# TUSB8041_Misc_2.net
KiCad netlist of a schematic drawn in Altium Designer
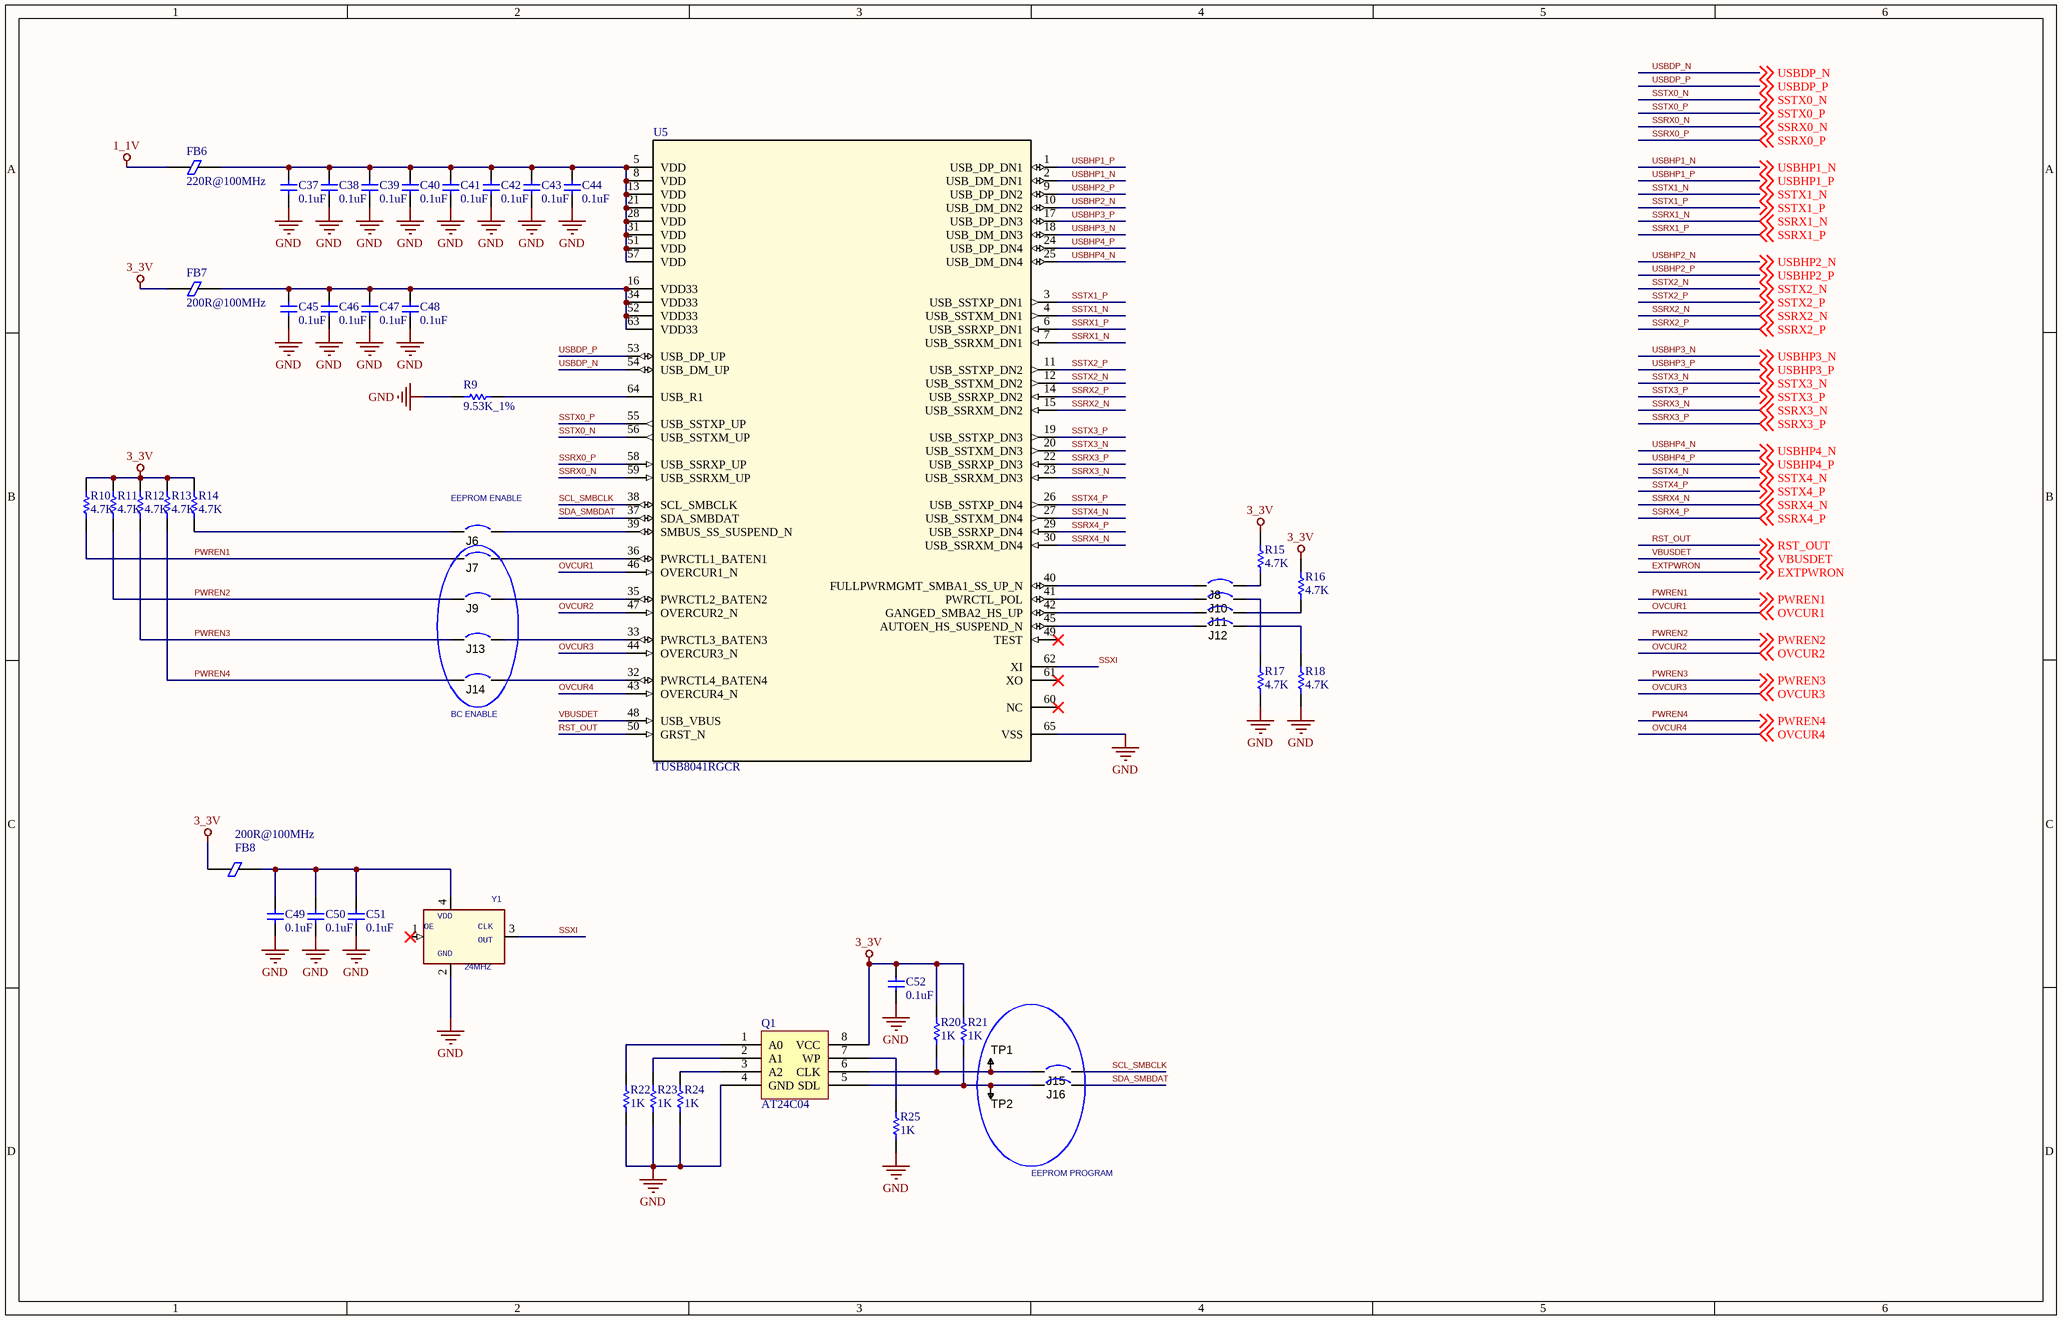
[diagram p0: TUSB8041_Misc_2.SchDoc]

(export (version "E")
  (design (tool "Eeschema 10.0.6"))
  (components
    (comp (ref "C37")
      (value "0.1uF")
      (footprint "CAP0402")
      (description "Capacitor")
      (fields (field (name "PUBLISHER") "Altium Limited"))
      (libsource (lib "TUSB8041_USB_3.0_Hub") (part "CAP"))
    )
    (comp (ref "C38")
      (value "0.1uF")
      (footprint "CAP0402")
      (description "Capacitor")
      (fields (field (name "PUBLISHER") "Altium Limited"))
      (libsource (lib "TUSB8041_USB_3.0_Hub") (part "CAP"))
    )
    (comp (ref "C39")
      (value "0.1uF")
      (footprint "CAP0402")
      (description "Capacitor")
      (fields (field (name "PUBLISHER") "Altium Limited"))
      (libsource (lib "TUSB8041_USB_3.0_Hub") (part "CAP"))
    )
    (comp (ref "C40")
      (value "0.1uF")
      (footprint "CAP0402")
      (description "Capacitor")
      (fields (field (name "PUBLISHER") "Altium Limited"))
      (libsource (lib "TUSB8041_USB_3.0_Hub") (part "CAP"))
    )
    (comp (ref "C41")
      (value "0.1uF")
      (footprint "CAP0402")
      (description "Capacitor")
      (fields (field (name "PUBLISHER") "Altium Limited"))
      (libsource (lib "TUSB8041_USB_3.0_Hub") (part "CAP"))
    )
    (comp (ref "C42")
      (value "0.1uF")
      (footprint "CAP0402")
      (description "Capacitor")
      (fields (field (name "PUBLISHER") "Altium Limited"))
      (libsource (lib "TUSB8041_USB_3.0_Hub") (part "CAP"))
    )
    (comp (ref "C43")
      (value "0.1uF")
      (footprint "CAP0402")
      (description "Capacitor")
      (fields (field (name "PUBLISHER") "Altium Limited"))
      (libsource (lib "TUSB8041_USB_3.0_Hub") (part "CAP"))
    )
    (comp (ref "C44")
      (value "0.1uF")
      (footprint "CAP0402")
      (description "Capacitor")
      (fields (field (name "PUBLISHER") "Altium Limited"))
      (libsource (lib "TUSB8041_USB_3.0_Hub") (part "CAP"))
    )
    (comp (ref "C45")
      (value "0.1uF")
      (footprint "CAP0402")
      (description "Capacitor")
      (fields (field (name "PUBLISHER") "Altium Limited"))
      (libsource (lib "TUSB8041_USB_3.0_Hub") (part "CAP"))
    )
    (comp (ref "C46")
      (value "0.1uF")
      (footprint "CAP0402")
      (description "Capacitor")
      (fields (field (name "PUBLISHER") "Altium Limited"))
      (libsource (lib "TUSB8041_USB_3.0_Hub") (part "CAP"))
    )
    (comp (ref "C47")
      (value "0.1uF")
      (footprint "CAP0402")
      (description "Capacitor")
      (fields (field (name "PUBLISHER") "Altium Limited"))
      (libsource (lib "TUSB8041_USB_3.0_Hub") (part "CAP"))
    )
    (comp (ref "C48")
      (value "0.1uF")
      (footprint "CAP0402")
      (description "Capacitor")
      (fields (field (name "PUBLISHER") "Altium Limited"))
      (libsource (lib "TUSB8041_USB_3.0_Hub") (part "CAP"))
    )
    (comp (ref "C49")
      (value "0.1uF")
      (footprint "CAP0603")
      (description "Capacitor")
      (fields (field (name "PUBLISHER") "Altium Limited"))
      (libsource (lib "TUSB8041_USB_3.0_Hub") (part "CAP"))
    )
    (comp (ref "C50")
      (value "0.1uF")
      (footprint "CAP0603")
      (description "Capacitor")
      (fields (field (name "PUBLISHER") "Altium Limited"))
      (libsource (lib "TUSB8041_USB_3.0_Hub") (part "CAP"))
    )
    (comp (ref "C51")
      (value "0.1uF")
      (footprint "CAP0603")
      (description "Capacitor")
      (fields (field (name "PUBLISHER") "Altium Limited"))
      (libsource (lib "TUSB8041_USB_3.0_Hub") (part "CAP"))
    )
    (comp (ref "C52")
      (value "0.1uF")
      (footprint "CAP0603")
      (description "Capacitor")
      (fields (field (name "PUBLISHER") "Altium Limited"))
      (libsource (lib "TUSB8041_USB_3.0_Hub") (part "CAP"))
    )
    (comp (ref "FB6")
      (value "220R@100MHz")
      (footprint "L0603")
      (libsource (lib "TUSB8041_USB_3.0_Hub") (part "Ferrite Bead"))
    )
    (comp (ref "FB7")
      (value "200R@100MHz")
      (footprint "L0603")
      (libsource (lib "TUSB8041_USB_3.0_Hub") (part "Ferrite Bead"))
    )
    (comp (ref "FB8")
      (value "200R@100MHz")
      (footprint "L0603")
      (libsource (lib "TUSB8041_USB_3.0_Hub") (part "Ferrite Bead"))
    )
    (comp (ref "J6")
      (value "JUMPER")
      (footprint "JP")
      (fields (field (name "MANUFACTURER") "Used in BOM report") (field (name "SYMBOLCREATOR") "Use a-id"))
      (libsource (lib "TUSB8041_USB_3.0_Hub") (part "JUMPER"))
    )
    (comp (ref "J7")
      (value "JUMPER")
      (footprint "JP")
      (fields (field (name "MANUFACTURER") "Used in BOM report") (field (name "SYMBOLCREATOR") "Use a-id"))
      (libsource (lib "TUSB8041_USB_3.0_Hub") (part "JUMPER"))
    )
    (comp (ref "J8")
      (value "JUMPER")
      (footprint "JP")
      (fields (field (name "MANUFACTURER") "Used in BOM report") (field (name "SYMBOLCREATOR") "Use a-id"))
      (libsource (lib "TUSB8041_USB_3.0_Hub") (part "JUMPER"))
    )
    (comp (ref "J9")
      (value "JUMPER")
      (footprint "JP")
      (fields (field (name "MANUFACTURER") "Used in BOM report") (field (name "SYMBOLCREATOR") "Use a-id"))
      (libsource (lib "TUSB8041_USB_3.0_Hub") (part "JUMPER"))
    )
    (comp (ref "J10")
      (value "JUMPER")
      (footprint "JP")
      (fields (field (name "MANUFACTURER") "Used in BOM report") (field (name "SYMBOLCREATOR") "Use a-id"))
      (libsource (lib "TUSB8041_USB_3.0_Hub") (part "JUMPER"))
    )
    (comp (ref "J11")
      (value "JUMPER")
      (footprint "JP")
      (fields (field (name "MANUFACTURER") "Used in BOM report") (field (name "SYMBOLCREATOR") "Use a-id"))
      (libsource (lib "TUSB8041_USB_3.0_Hub") (part "JUMPER"))
    )
    (comp (ref "J12")
      (value "JUMPER")
      (footprint "JP")
      (fields (field (name "MANUFACTURER") "Used in BOM report") (field (name "SYMBOLCREATOR") "Use a-id"))
      (libsource (lib "TUSB8041_USB_3.0_Hub") (part "JUMPER"))
    )
    (comp (ref "J13")
      (value "JUMPER")
      (footprint "JP")
      (fields (field (name "MANUFACTURER") "Used in BOM report") (field (name "SYMBOLCREATOR") "Use a-id"))
      (libsource (lib "TUSB8041_USB_3.0_Hub") (part "JUMPER"))
    )
    (comp (ref "J14")
      (value "JUMPER")
      (footprint "JP")
      (fields (field (name "MANUFACTURER") "Used in BOM report") (field (name "SYMBOLCREATOR") "Use a-id"))
      (libsource (lib "TUSB8041_USB_3.0_Hub") (part "JUMPER"))
    )
    (comp (ref "J15")
      (value "JUMPER")
      (footprint "JP")
      (fields (field (name "MANUFACTURER") "Used in BOM report") (field (name "SYMBOLCREATOR") "Use a-id"))
      (libsource (lib "TUSB8041_USB_3.0_Hub") (part "JUMPER"))
    )
    (comp (ref "J16")
      (value "JUMPER")
      (footprint "JP")
      (fields (field (name "MANUFACTURER") "Used in BOM report") (field (name "SYMBOLCREATOR") "Use a-id"))
      (libsource (lib "TUSB8041_USB_3.0_Hub") (part "JUMPER"))
    )
    (comp (ref "Q1")
      (value "AT24C04")
      (footprint "SOIC-8")
      (description "I2C-Compatible, (2-wire) Serial EEPROM\r\n4-Kbit (512 x 8)")
      (libsource (lib "TUSB8041_USB_3.0_Hub") (part "AT24C04"))
    )
    (comp (ref "R9")
      (value "9.53K_1%")
      (footprint "RES0603")
      (description "Resistor")
      (fields (field (name "PUBLISHER") "Altium Limited"))
      (libsource (lib "TUSB8041_USB_3.0_Hub") (part "RES"))
    )
    (comp (ref "R10")
      (value "4.7K")
      (footprint "RES0603")
      (description "Resistor")
      (fields (field (name "PUBLISHER") "Altium Limited"))
      (libsource (lib "TUSB8041_USB_3.0_Hub") (part "RES"))
    )
    (comp (ref "R11")
      (value "4.7K")
      (footprint "RES0603")
      (description "Resistor")
      (fields (field (name "PUBLISHER") "Altium Limited"))
      (libsource (lib "TUSB8041_USB_3.0_Hub") (part "RES"))
    )
    (comp (ref "R12")
      (value "4.7K")
      (footprint "RES0603")
      (description "Resistor")
      (fields (field (name "PUBLISHER") "Altium Limited"))
      (libsource (lib "TUSB8041_USB_3.0_Hub") (part "RES"))
    )
    (comp (ref "R13")
      (value "4.7K")
      (footprint "RES0603")
      (description "Resistor")
      (fields (field (name "PUBLISHER") "Altium Limited"))
      (libsource (lib "TUSB8041_USB_3.0_Hub") (part "RES"))
    )
    (comp (ref "R14")
      (value "4.7K")
      (footprint "RES0603")
      (description "Resistor")
      (fields (field (name "PUBLISHER") "Altium Limited"))
      (libsource (lib "TUSB8041_USB_3.0_Hub") (part "RES"))
    )
    (comp (ref "R15")
      (value "4.7K")
      (footprint "RES0603")
      (description "Resistor")
      (fields (field (name "PUBLISHER") "Altium Limited"))
      (libsource (lib "TUSB8041_USB_3.0_Hub") (part "RES"))
    )
    (comp (ref "R16")
      (value "4.7K")
      (footprint "RES0603")
      (description "Resistor")
      (fields (field (name "PUBLISHER") "Altium Limited"))
      (libsource (lib "TUSB8041_USB_3.0_Hub") (part "RES"))
    )
    (comp (ref "R17")
      (value "4.7K")
      (footprint "RES0603")
      (description "Resistor")
      (fields (field (name "PUBLISHER") "Altium Limited"))
      (libsource (lib "TUSB8041_USB_3.0_Hub") (part "RES"))
    )
    (comp (ref "R18")
      (value "4.7K")
      (footprint "RES0603")
      (description "Resistor")
      (fields (field (name "PUBLISHER") "Altium Limited"))
      (libsource (lib "TUSB8041_USB_3.0_Hub") (part "RES"))
    )
    (comp (ref "R20")
      (value "1K")
      (footprint "RES0603")
      (description "Resistor")
      (fields (field (name "PUBLISHER") "Altium Limited"))
      (libsource (lib "TUSB8041_USB_3.0_Hub") (part "RES"))
    )
    (comp (ref "R21")
      (value "1K")
      (footprint "RES0603")
      (description "Resistor")
      (fields (field (name "PUBLISHER") "Altium Limited"))
      (libsource (lib "TUSB8041_USB_3.0_Hub") (part "RES"))
    )
    (comp (ref "R22")
      (value "1K")
      (footprint "RES0603")
      (description "Resistor")
      (fields (field (name "PUBLISHER") "Altium Limited"))
      (libsource (lib "TUSB8041_USB_3.0_Hub") (part "RES"))
    )
    (comp (ref "R23")
      (value "1K")
      (footprint "RES0603")
      (description "Resistor")
      (fields (field (name "PUBLISHER") "Altium Limited"))
      (libsource (lib "TUSB8041_USB_3.0_Hub") (part "RES"))
    )
    (comp (ref "R24")
      (value "1K")
      (footprint "RES0603")
      (description "Resistor")
      (fields (field (name "PUBLISHER") "Altium Limited"))
      (libsource (lib "TUSB8041_USB_3.0_Hub") (part "RES"))
    )
    (comp (ref "R25")
      (value "1K")
      (footprint "RES0603")
      (description "Resistor")
      (fields (field (name "PUBLISHER") "Altium Limited"))
      (libsource (lib "TUSB8041_USB_3.0_Hub") (part "RES"))
    )
    (comp (ref "TP1")
      (value "TESTPOINT_THT_MINI")
      (footprint "TP")
      (description "Test Point")
      (libsource (lib "TUSB8041_USB_3.0_Hub") (part "TESTPOINT_THT_MINI"))
    )
    (comp (ref "TP2")
      (value "TESTPOINT_THT_MINI")
      (footprint "TP")
      (description "Test Point")
      (libsource (lib "TUSB8041_USB_3.0_Hub") (part "TESTPOINT_THT_MINI"))
    )
    (comp (ref "U5")
      (value "TUSB8041RGCR")
      (footprint "QFN64_9*9")
      (description "USB30HUB")
      (fields
        (field (name "ALTERNATE PARTNUMBER") "TUSB8041RGCT")
        (field (name "MANUFACTURER") "Texas Instruments")
      )
      (libsource (lib "TUSB8041_USB_3.0_Hub") (part "TUSB8041RGCR"))
    )
    (comp (ref "Y1")
      (value "24MHZ")
      (footprint "XTAL-3225")
      (description "OSC 50MHZ FIXED 3.3V SMT")
      (libsource (lib "小车") (part "XTAL"))
    )
  )
  (nets
    (net (code "1") (name "/SCL_SMBCLK") (class "Default")
      (node (ref "J15") (pin "2") (pinfunction "2_2") (pintype "passive"))
      (node (ref "U5") (pin "38") (pinfunction "SCL_SMBCLK_38") (pintype "bidirectional"))
    )
    (net (code "2") (name "/SDA_SMBDAT") (class "Default")
      (node (ref "J16") (pin "2") (pinfunction "2_2") (pintype "passive"))
      (node (ref "U5") (pin "37") (pinfunction "SDA_SMBDAT_37") (pintype "bidirectional"))
    )
    (net (code "3") (name "/SSXI") (class "Default")
      (node (ref "U5") (pin "62") (pinfunction "XI_62") (pintype "passive"))
      (node (ref "Y1") (pin "3") (pinfunction "CLKOUT_3") (pintype "tri_state"))
    )
    (net (code "4") (name "1_1V") (class "Default") (node (ref "FB6") (pin "2") (pintype "passive")))
    (net (code "5") (name "3_3V") (class "Default")
      (node (ref "C52") (pin "2") (pinfunction "2_2") (pintype "passive"))
      (node (ref "FB7") (pin "2") (pintype "passive"))
      (node (ref "FB8") (pin "2") (pintype "passive"))
      (node (ref "Q1") (pin "8") (pinfunction "VCC_8") (pintype "passive"))
      (node (ref "R10") (pin "2") (pinfunction "2_2") (pintype "passive"))
      (node (ref "R11") (pin "2") (pinfunction "2_2") (pintype "passive"))
      (node (ref "R12") (pin "2") (pinfunction "2_2") (pintype "passive"))
      (node (ref "R13") (pin "2") (pinfunction "2_2") (pintype "passive"))
      (node (ref "R14") (pin "2") (pinfunction "2_2") (pintype "passive"))
      (node (ref "R15") (pin "2") (pinfunction "2_2") (pintype "passive"))
      (node (ref "R16") (pin "2") (pinfunction "2_2") (pintype "passive"))
      (node (ref "R20") (pin "2") (pinfunction "2_2") (pintype "passive"))
      (node (ref "R21") (pin "2") (pinfunction "2_2") (pintype "passive"))
    )
    (net (code "7") (name "GND") (class "Default")
      (node (ref "C37") (pin "1") (pinfunction "1_1") (pintype "passive"))
      (node (ref "C38") (pin "1") (pinfunction "1_1") (pintype "passive"))
      (node (ref "C39") (pin "1") (pinfunction "1_1") (pintype "passive"))
      (node (ref "C40") (pin "1") (pinfunction "1_1") (pintype "passive"))
      (node (ref "C41") (pin "1") (pinfunction "1_1") (pintype "passive"))
      (node (ref "C42") (pin "1") (pinfunction "1_1") (pintype "passive"))
      (node (ref "C43") (pin "1") (pinfunction "1_1") (pintype "passive"))
      (node (ref "C44") (pin "1") (pinfunction "1_1") (pintype "passive"))
      (node (ref "C45") (pin "1") (pinfunction "1_1") (pintype "passive"))
      (node (ref "C46") (pin "1") (pinfunction "1_1") (pintype "passive"))
      (node (ref "C47") (pin "1") (pinfunction "1_1") (pintype "passive"))
      (node (ref "C48") (pin "1") (pinfunction "1_1") (pintype "passive"))
      (node (ref "C49") (pin "1") (pinfunction "1_1") (pintype "passive"))
      (node (ref "C50") (pin "1") (pinfunction "1_1") (pintype "passive"))
      (node (ref "C51") (pin "1") (pinfunction "1_1") (pintype "passive"))
      (node (ref "C52") (pin "1") (pinfunction "1_1") (pintype "passive"))
      (node (ref "Q1") (pin "4") (pinfunction "GND_4") (pintype "passive"))
      (node (ref "R17") (pin "1") (pinfunction "1_1") (pintype "passive"))
      (node (ref "R18") (pin "1") (pinfunction "1_1") (pintype "passive"))
      (node (ref "R22") (pin "1") (pinfunction "1_1") (pintype "passive"))
      (node (ref "R23") (pin "1") (pinfunction "1_1") (pintype "passive"))
      (node (ref "R24") (pin "1") (pinfunction "1_1") (pintype "passive"))
      (node (ref "R25") (pin "1") (pinfunction "1_1") (pintype "passive"))
      (node (ref "R9") (pin "2") (pinfunction "2_2") (pintype "passive"))
      (node (ref "U5") (pin "65") (pinfunction "VSS_65") (pintype "power_in"))
      (node (ref "Y1") (pin "2") (pinfunction "GND_2") (pintype "power_in"))
    )
    (net (code "8") (name "Net-(C37-Pad2)") (class "Default")
      (node (ref "C37") (pin "2") (pinfunction "2_2") (pintype "passive"))
      (node (ref "C38") (pin "2") (pinfunction "2_2") (pintype "passive"))
      (node (ref "C39") (pin "2") (pinfunction "2_2") (pintype "passive"))
      (node (ref "C40") (pin "2") (pinfunction "2_2") (pintype "passive"))
      (node (ref "C41") (pin "2") (pinfunction "2_2") (pintype "passive"))
      (node (ref "C42") (pin "2") (pinfunction "2_2") (pintype "passive"))
      (node (ref "C43") (pin "2") (pinfunction "2_2") (pintype "passive"))
      (node (ref "C44") (pin "2") (pinfunction "2_2") (pintype "passive"))
      (node (ref "FB6") (pin "1") (pintype "passive"))
      (node (ref "U5") (pin "13") (pinfunction "VDD_13") (pintype "power_in"))
      (node (ref "U5") (pin "21") (pinfunction "VDD_21") (pintype "power_in"))
      (node (ref "U5") (pin "28") (pinfunction "VDD_28") (pintype "power_in"))
      (node (ref "U5") (pin "31") (pinfunction "VDD_31") (pintype "power_in"))
      (node (ref "U5") (pin "5") (pinfunction "VDD_5") (pintype "power_in"))
      (node (ref "U5") (pin "51") (pinfunction "VDD_51") (pintype "power_in"))
      (node (ref "U5") (pin "57") (pinfunction "VDD_57") (pintype "power_in"))
      (node (ref "U5") (pin "8") (pinfunction "VDD_8") (pintype "power_in"))
    )
    (net (code "9") (name "Net-(C45-Pad2)") (class "Default")
      (node (ref "C45") (pin "2") (pinfunction "2_2") (pintype "passive"))
      (node (ref "C46") (pin "2") (pinfunction "2_2") (pintype "passive"))
      (node (ref "C47") (pin "2") (pinfunction "2_2") (pintype "passive"))
      (node (ref "C48") (pin "2") (pinfunction "2_2") (pintype "passive"))
      (node (ref "FB7") (pin "1") (pintype "passive"))
      (node (ref "U5") (pin "16") (pinfunction "VDD33_16") (pintype "power_in"))
      (node (ref "U5") (pin "34") (pinfunction "VDD33_34") (pintype "power_in"))
      (node (ref "U5") (pin "52") (pinfunction "VDD33_52") (pintype "power_in"))
      (node (ref "U5") (pin "63") (pinfunction "VDD33_63") (pintype "power_in"))
    )
    (net (code "10") (name "Net-(J6-Pad1)") (class "Default")
      (node (ref "J6") (pin "1") (pinfunction "1_1") (pintype "passive"))
      (node (ref "R14") (pin "1") (pinfunction "1_1") (pintype "passive"))
    )
    (net (code "11") (name "Net-(J8-Pad2)") (class "Default")
      (node (ref "J8") (pin "2") (pinfunction "2_2") (pintype "passive"))
      (node (ref "R15") (pin "1") (pinfunction "1_1") (pintype "passive"))
    )
    (net (code "12") (name "Net-(J10-Pad2)") (class "Default")
      (node (ref "J10") (pin "2") (pinfunction "2_2") (pintype "passive"))
      (node (ref "R17") (pin "2") (pinfunction "2_2") (pintype "passive"))
    )
    (net (code "13") (name "Net-(J11-Pad2)") (class "Default")
      (node (ref "J11") (pin "2") (pinfunction "2_2") (pintype "passive"))
      (node (ref "R16") (pin "1") (pinfunction "1_1") (pintype "passive"))
    )
    (net (code "14") (name "Net-(J12-Pad2)") (class "Default")
      (node (ref "J12") (pin "2") (pinfunction "2_2") (pintype "passive"))
      (node (ref "R18") (pin "2") (pinfunction "2_2") (pintype "passive"))
    )
    (net (code "15") (name "Net-(Q1-A0)") (class "Default")
      (node (ref "Q1") (pin "1") (pinfunction "A0_1") (pintype "passive"))
      (node (ref "R22") (pin "2") (pinfunction "2_2") (pintype "passive"))
    )
    (net (code "16") (name "Net-(Q1-A1)") (class "Default")
      (node (ref "Q1") (pin "2") (pinfunction "A1_2") (pintype "passive"))
      (node (ref "R23") (pin "2") (pinfunction "2_2") (pintype "passive"))
    )
    (net (code "17") (name "Net-(Q1-A2)") (class "Default")
      (node (ref "Q1") (pin "3") (pinfunction "A2_3") (pintype "passive"))
      (node (ref "R24") (pin "2") (pinfunction "2_2") (pintype "passive"))
    )
    (net (code "18") (name "Net-(Q1-CLK)") (class "Default")
      (node (ref "J15") (pin "1") (pinfunction "1_1") (pintype "passive"))
      (node (ref "Q1") (pin "6") (pinfunction "CLK_6") (pintype "passive"))
      (node (ref "R20") (pin "1") (pinfunction "1_1") (pintype "passive"))
      (node (ref "TP1") (pin "1") (pintype "passive"))
    )
    (net (code "19") (name "Net-(Q1-SDL)") (class "Default")
      (node (ref "J16") (pin "1") (pinfunction "1_1") (pintype "passive"))
      (node (ref "Q1") (pin "5") (pinfunction "SDL_5") (pintype "passive"))
      (node (ref "R21") (pin "1") (pinfunction "1_1") (pintype "passive"))
      (node (ref "TP2") (pin "1") (pintype "passive"))
    )
    (net (code "20") (name "Net-(Q1-WP)") (class "Default")
      (node (ref "Q1") (pin "7") (pinfunction "WP_7") (pintype "passive"))
      (node (ref "R25") (pin "2") (pinfunction "2_2") (pintype "passive"))
    )
    (net (code "21") (name "Net-(U5-AUTOEN_HS_SUSPEND_N)") (class "Default")
      (node (ref "J12") (pin "1") (pinfunction "1_1") (pintype "passive"))
      (node (ref "U5") (pin "45") (pinfunction "AUTOEN_HS_SUSPEND_N_45") (pintype "bidirectional"))
    )
    (net (code "22") (name "Net-(U5-FULLPWRMGMT_SMBA1_SS_UP_N)") (class "Default")
      (node (ref "J8") (pin "1") (pinfunction "1_1") (pintype "passive"))
      (node (ref "U5") (pin "40") (pinfunction "FULLPWRMGMT_SMBA1_SS_UP_N_40") (pintype "bidirectional"))
    )
    (net (code "23") (name "Net-(U5-GANGED_SMBA2_HS_UP)") (class "Default")
      (node (ref "J11") (pin "1") (pinfunction "1_1") (pintype "passive"))
      (node (ref "U5") (pin "42") (pinfunction "GANGED_SMBA2_HS_UP_42") (pintype "bidirectional"))
    )
    (net (code "24") (name "Net-(U5-PWRCTL1_BATEN1)") (class "Default")
      (node (ref "J7") (pin "2") (pinfunction "2_2") (pintype "passive"))
      (node (ref "U5") (pin "36") (pinfunction "PWRCTL1_BATEN1_36") (pintype "bidirectional"))
    )
    (net (code "25") (name "Net-(U5-PWRCTL2_BATEN2)") (class "Default")
      (node (ref "J9") (pin "2") (pinfunction "2_2") (pintype "passive"))
      (node (ref "U5") (pin "35") (pinfunction "PWRCTL2_BATEN2_35") (pintype "bidirectional"))
    )
    (net (code "26") (name "Net-(U5-PWRCTL3_BATEN3)") (class "Default")
      (node (ref "J13") (pin "2") (pinfunction "2_2") (pintype "passive"))
      (node (ref "U5") (pin "33") (pinfunction "PWRCTL3_BATEN3_33") (pintype "bidirectional"))
    )
    (net (code "27") (name "Net-(U5-PWRCTL4_BATEN4)") (class "Default")
      (node (ref "J14") (pin "2") (pinfunction "2_2") (pintype "passive"))
      (node (ref "U5") (pin "32") (pinfunction "PWRCTL4_BATEN4_32") (pintype "bidirectional"))
    )
    (net (code "28") (name "Net-(U5-PWRCTL_POL)") (class "Default")
      (node (ref "J10") (pin "1") (pinfunction "1_1") (pintype "passive"))
      (node (ref "U5") (pin "41") (pinfunction "PWRCTL_POL_41") (pintype "bidirectional"))
    )
    (net (code "29") (name "Net-(U5-SMBUS_SS_SUSPEND_N)") (class "Default")
      (node (ref "J6") (pin "2") (pinfunction "2_2") (pintype "passive"))
      (node (ref "U5") (pin "39") (pinfunction "SMBUS_SS_SUSPEND_N_39") (pintype "bidirectional"))
    )
    (net (code "30") (name "Net-(U5-USB_R1)") (class "Default")
      (node (ref "R9") (pin "1") (pinfunction "1_1") (pintype "passive"))
      (node (ref "U5") (pin "64") (pinfunction "USB_R1_64") (pintype "passive"))
    )
    (net (code "31") (name "Net-(Y1-VDD)") (class "Default")
      (node (ref "C49") (pin "2") (pinfunction "2_2") (pintype "passive"))
      (node (ref "C50") (pin "2") (pinfunction "2_2") (pintype "passive"))
      (node (ref "C51") (pin "2") (pinfunction "2_2") (pintype "passive"))
      (node (ref "FB8") (pin "1") (pintype "passive"))
      (node (ref "Y1") (pin "4") (pinfunction "VDD_4") (pintype "power_in"))
    )
    (net (code "32") (name "OVCUR1") (class "Default")
      (node (ref "U5") (pin "46") (pinfunction "OVERCUR1_N_46") (pintype "input"))
    )
    (net (code "33") (name "OVCUR2") (class "Default")
      (node (ref "U5") (pin "47") (pinfunction "OVERCUR2_N_47") (pintype "input"))
    )
    (net (code "34") (name "OVCUR3") (class "Default")
      (node (ref "U5") (pin "44") (pinfunction "OVERCUR3_N_44") (pintype "input"))
    )
    (net (code "35") (name "OVCUR4") (class "Default")
      (node (ref "U5") (pin "43") (pinfunction "OVERCUR4_N_43") (pintype "input"))
    )
    (net (code "36") (name "PWREN1") (class "Default")
      (node (ref "J7") (pin "1") (pinfunction "1_1") (pintype "passive"))
      (node (ref "R10") (pin "1") (pinfunction "1_1") (pintype "passive"))
    )
    (net (code "37") (name "PWREN2") (class "Default")
      (node (ref "J9") (pin "1") (pinfunction "1_1") (pintype "passive"))
      (node (ref "R11") (pin "1") (pinfunction "1_1") (pintype "passive"))
    )
    (net (code "38") (name "PWREN3") (class "Default")
      (node (ref "J13") (pin "1") (pinfunction "1_1") (pintype "passive"))
      (node (ref "R12") (pin "1") (pinfunction "1_1") (pintype "passive"))
    )
    (net (code "39") (name "PWREN4") (class "Default")
      (node (ref "J14") (pin "1") (pinfunction "1_1") (pintype "passive"))
      (node (ref "R13") (pin "1") (pinfunction "1_1") (pintype "passive"))
    )
    (net (code "40") (name "RST_OUT") (class "Default")
      (node (ref "U5") (pin "50") (pinfunction "GRST_N_50") (pintype "input"))
    )
    (net (code "41") (name "SSRX0_N") (class "Default")
      (node (ref "U5") (pin "59") (pinfunction "USB_SSRXM_UP_59") (pintype "input"))
    )
    (net (code "42") (name "SSRX0_P") (class "Default")
      (node (ref "U5") (pin "58") (pinfunction "USB_SSRXP_UP_58") (pintype "input"))
    )
    (net (code "43") (name "SSRX1_N") (class "Default")
      (node (ref "U5") (pin "7") (pinfunction "USB_SSRXM_DN1_7") (pintype "input"))
    )
    (net (code "44") (name "SSRX1_P") (class "Default")
      (node (ref "U5") (pin "6") (pinfunction "USB_SSRXP_DN1_6") (pintype "input"))
    )
    (net (code "45") (name "SSRX2_N") (class "Default")
      (node (ref "U5") (pin "15") (pinfunction "USB_SSRXM_DN2_15") (pintype "input"))
    )
    (net (code "46") (name "SSRX2_P") (class "Default")
      (node (ref "U5") (pin "14") (pinfunction "USB_SSRXP_DN2_14") (pintype "input"))
    )
    (net (code "47") (name "SSRX3_N") (class "Default")
      (node (ref "U5") (pin "23") (pinfunction "USB_SSRXM_DN3_23") (pintype "input"))
    )
    (net (code "48") (name "SSRX3_P") (class "Default")
      (node (ref "U5") (pin "22") (pinfunction "USB_SSRXP_DN3_22") (pintype "input"))
    )
    (net (code "49") (name "SSRX4_N") (class "Default")
      (node (ref "U5") (pin "30") (pinfunction "USB_SSRXM_DN4_30") (pintype "input"))
    )
    (net (code "50") (name "SSRX4_P") (class "Default")
      (node (ref "U5") (pin "29") (pinfunction "USB_SSRXP_DN4_29") (pintype "input"))
    )
    (net (code "51") (name "SSTX0_N") (class "Default")
      (node (ref "U5") (pin "56") (pinfunction "USB_SSTXM_UP_56") (pintype "output"))
    )
    (net (code "52") (name "SSTX0_P") (class "Default")
      (node (ref "U5") (pin "55") (pinfunction "USB_SSTXP_UP_55") (pintype "output"))
    )
    (net (code "53") (name "SSTX1_N") (class "Default")
      (node (ref "U5") (pin "4") (pinfunction "USB_SSTXM_DN1_4") (pintype "output"))
    )
    (net (code "54") (name "SSTX1_P") (class "Default")
      (node (ref "U5") (pin "3") (pinfunction "USB_SSTXP_DN1_3") (pintype "output"))
    )
    (net (code "55") (name "SSTX2_N") (class "Default")
      (node (ref "U5") (pin "12") (pinfunction "USB_SSTXM_DN2_12") (pintype "output"))
    )
    (net (code "56") (name "SSTX2_P") (class "Default")
      (node (ref "U5") (pin "11") (pinfunction "USB_SSTXP_DN2_11") (pintype "output"))
    )
    (net (code "57") (name "SSTX3_N") (class "Default")
      (node (ref "U5") (pin "20") (pinfunction "USB_SSTXM_DN3_20") (pintype "output"))
    )
    (net (code "58") (name "SSTX3_P") (class "Default")
      (node (ref "U5") (pin "19") (pinfunction "USB_SSTXP_DN3_19") (pintype "output"))
    )
    (net (code "59") (name "SSTX4_N") (class "Default")
      (node (ref "U5") (pin "27") (pinfunction "USB_SSTXM_DN4_27") (pintype "output"))
    )
    (net (code "60") (name "SSTX4_P") (class "Default")
      (node (ref "U5") (pin "26") (pinfunction "USB_SSTXP_DN4_26") (pintype "output"))
    )
    (net (code "61") (name "USBDP_N") (class "Default")
      (node (ref "U5") (pin "54") (pinfunction "USB_DM_UP_54") (pintype "bidirectional"))
    )
    (net (code "62") (name "USBDP_P") (class "Default")
      (node (ref "U5") (pin "53") (pinfunction "USB_DP_UP_53") (pintype "bidirectional"))
    )
    (net (code "63") (name "USBHP1_N") (class "Default")
      (node (ref "U5") (pin "2") (pinfunction "USB_DM_DN1_2") (pintype "bidirectional"))
    )
    (net (code "64") (name "USBHP1_P") (class "Default")
      (node (ref "U5") (pin "1") (pinfunction "USB_DP_DN1_1") (pintype "bidirectional"))
    )
    (net (code "65") (name "USBHP2_N") (class "Default")
      (node (ref "U5") (pin "10") (pinfunction "USB_DM_DN2_10") (pintype "bidirectional"))
    )
    (net (code "66") (name "USBHP2_P") (class "Default")
      (node (ref "U5") (pin "9") (pinfunction "USB_DP_DN2_9") (pintype "bidirectional"))
    )
    (net (code "67") (name "USBHP3_N") (class "Default")
      (node (ref "U5") (pin "18") (pinfunction "USB_DM_DN3_18") (pintype "bidirectional"))
    )
    (net (code "68") (name "USBHP3_P") (class "Default")
      (node (ref "U5") (pin "17") (pinfunction "USB_DP_DN3_17") (pintype "bidirectional"))
    )
    (net (code "69") (name "USBHP4_N") (class "Default")
      (node (ref "U5") (pin "25") (pinfunction "USB_DM_DN4_25") (pintype "bidirectional"))
    )
    (net (code "70") (name "USBHP4_P") (class "Default")
      (node (ref "U5") (pin "24") (pinfunction "USB_DP_DN4_24") (pintype "bidirectional"))
    )
    (net (code "71") (name "VBUSDET") (class "Default")
      (node (ref "U5") (pin "48") (pinfunction "USB_VBUS_48") (pintype "input"))
    )
    (net (code "72") (name "unconnected-(U5-NC-Pad60)") (class "Default")
      (node (ref "U5") (pin "60") (pinfunction "NC_60") (pintype "power_in+no_connect"))
    )
    (net (code "73") (name "unconnected-(U5-TEST-Pad49)") (class "Default")
      (node (ref "U5") (pin "49") (pinfunction "TEST_49") (pintype "input+no_connect"))
    )
    (net (code "74") (name "unconnected-(U5-XO-Pad61)") (class "Default")
      (node (ref "U5") (pin "61") (pinfunction "XO_61") (pintype "passive+no_connect"))
    )
    (net (code "75") (name "unconnected-(Y1-OE-Pad1)") (class "Default")
      (node (ref "Y1") (pin "1") (pinfunction "OE_1") (pintype "input+no_connect"))
    )
  )
)
